# obc-v2_CM4-PinOut.net
KiCad netlist of a schematic drawn in Altium Designer
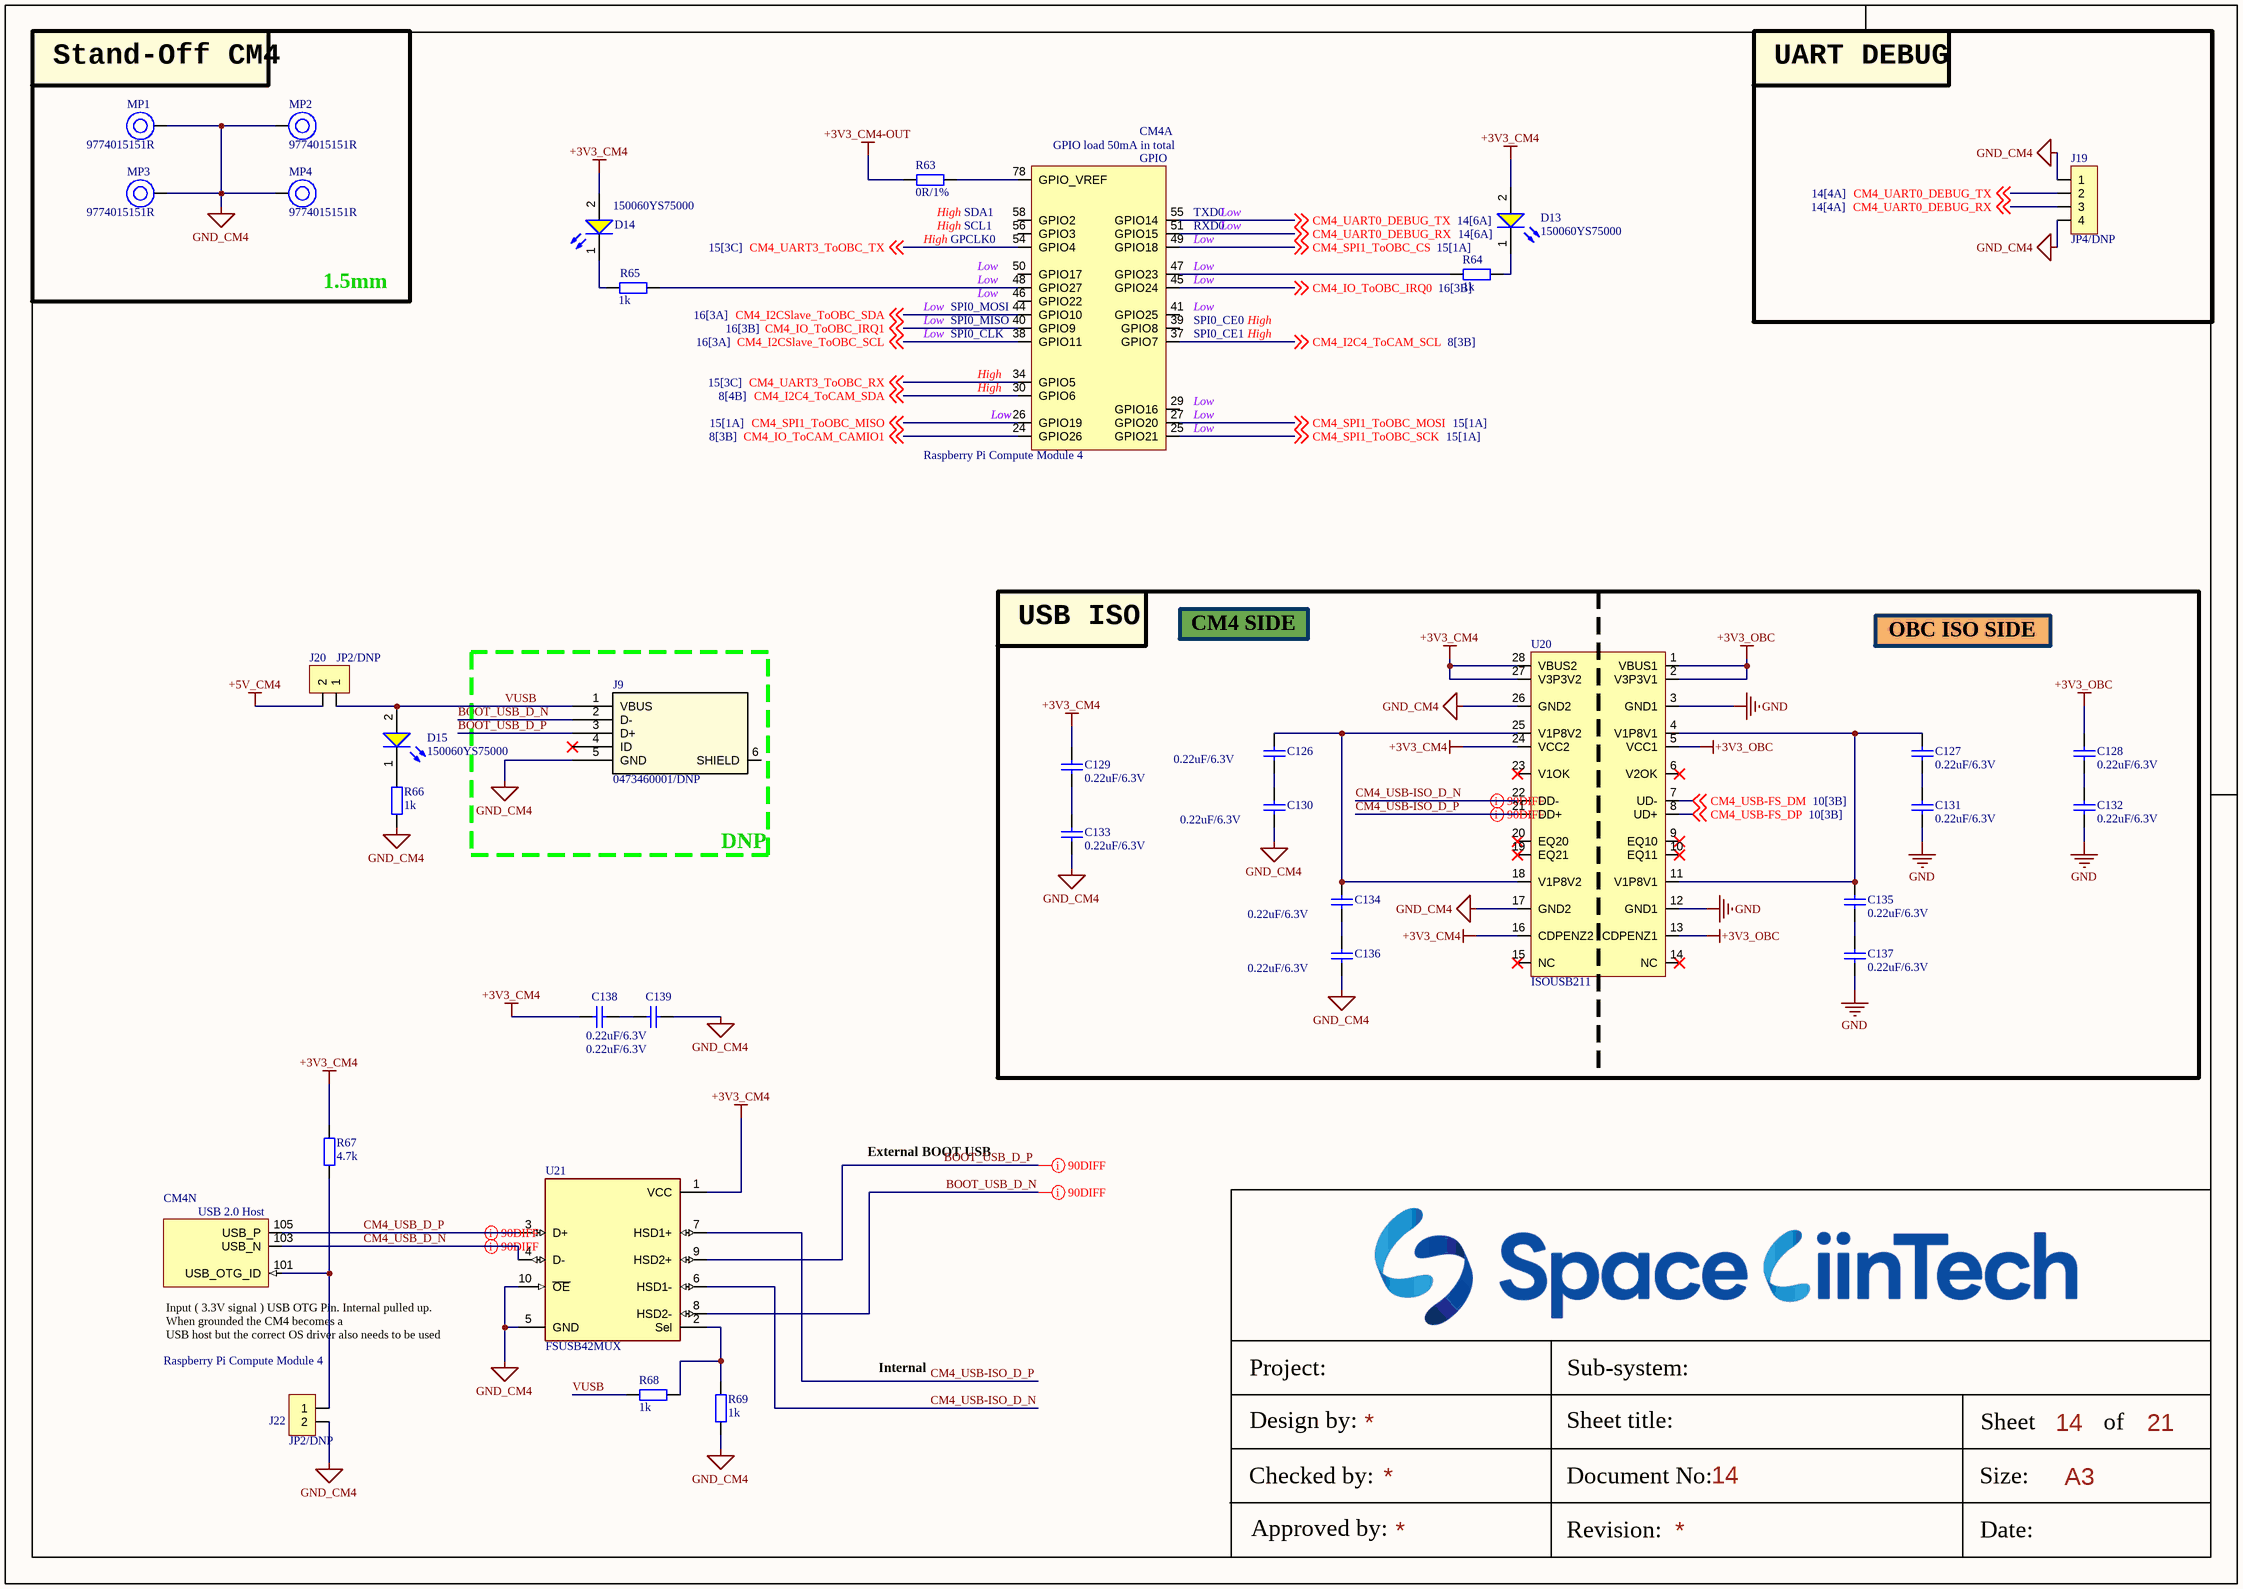
[diagram p0: obc-v2_CM4-PinOut.SchDoc]

(export (version "E")
  (design (tool "Eeschema 10.0.6"))
  (components
    (comp (ref "C126")
      (value "0.22uF/6.3V")
      (footprint "CAP_C_1005X60")
      (description "CAPC")
      (libsource (lib "Altium_Lib_by_KhueNguyenCreator") (part "Tu 0402 33nF 10V"))
    )
    (comp (ref "C127")
      (value "0.22uF/6.3V")
      (footprint "CAP_C_1005X60")
      (description "CAPC")
      (libsource (lib "Altium_Lib_by_KhueNguyenCreator") (part "Tu 0402 33nF 10V"))
    )
    (comp (ref "C128")
      (value "0.22uF/6.3V")
      (footprint "CAP_C_1005X60")
      (description "CAPC")
      (libsource (lib "Altium_Lib_by_KhueNguyenCreator") (part "Tu 0402 33nF 10V"))
    )
    (comp (ref "C129")
      (value "0.22uF/6.3V")
      (footprint "CAP_C_1005X60")
      (description "CAPC")
      (libsource (lib "Altium_Lib_by_KhueNguyenCreator") (part "Tu 0402 33nF 10V"))
    )
    (comp (ref "C130")
      (value "0.22uF/6.3V")
      (footprint "CAP_C_1005X60")
      (description "CAPC")
      (libsource (lib "Altium_Lib_by_KhueNguyenCreator") (part "Tu 0402 33nF 10V"))
    )
    (comp (ref "C131")
      (value "0.22uF/6.3V")
      (footprint "CAP_C_1005X60")
      (description "CAPC")
      (libsource (lib "Altium_Lib_by_KhueNguyenCreator") (part "Tu 0402 33nF 10V"))
    )
    (comp (ref "C132")
      (value "0.22uF/6.3V")
      (footprint "CAP_C_1005X60")
      (description "CAPC")
      (libsource (lib "Altium_Lib_by_KhueNguyenCreator") (part "Tu 0402 33nF 10V"))
    )
    (comp (ref "C133")
      (value "0.22uF/6.3V")
      (footprint "CAP_C_1005X60")
      (description "CAPC")
      (libsource (lib "Altium_Lib_by_KhueNguyenCreator") (part "Tu 0402 33nF 10V"))
    )
    (comp (ref "C134")
      (value "0.22uF/6.3V")
      (footprint "CAP_C_1005X60")
      (description "CAPC")
      (libsource (lib "Altium_Lib_by_KhueNguyenCreator") (part "Tu 0402 33nF 10V"))
    )
    (comp (ref "C135")
      (value "0.22uF/6.3V")
      (footprint "CAP_C_1005X60")
      (description "CAPC")
      (libsource (lib "Altium_Lib_by_KhueNguyenCreator") (part "Tu 0402 33nF 10V"))
    )
    (comp (ref "C136")
      (value "0.22uF/6.3V")
      (footprint "CAP_C_1005X60")
      (description "CAPC")
      (libsource (lib "Altium_Lib_by_KhueNguyenCreator") (part "Tu 0402 33nF 10V"))
    )
    (comp (ref "C137")
      (value "0.22uF/6.3V")
      (footprint "CAP_C_1005X60")
      (description "CAPC")
      (libsource (lib "Altium_Lib_by_KhueNguyenCreator") (part "Tu 0402 33nF 10V"))
    )
    (comp (ref "C138")
      (value "0.22uF/6.3V")
      (footprint "CAP_C_1005X60")
      (description "CAPC")
      (libsource (lib "Altium_Lib_by_KhueNguyenCreator") (part "Tu 0402 33nF 10V"))
    )
    (comp (ref "C139")
      (value "0.22uF/6.3V")
      (footprint "CAP_C_1005X60")
      (description "CAPC")
      (libsource (lib "Altium_Lib_by_KhueNguyenCreator") (part "Tu 0402 33nF 10V"))
    )
    (comp (ref "CM4")
      (value "Raspberry Pi Compute Module 4")
      (footprint "CM4-DF40HC(3.0)-100DS-0.4v_3mm_1.5mm")
      (description "Raspberry Pi Compute Module 4 by Amornthep Phunsin")
      (libsource (lib "CM4") (part "CM4"))
    )
    (comp (ref "D13")
      (value "150060YS75000")
      (footprint "WL-SMCW_0603_150060xx75000")
      (description "LED YELLOW CLEAR 0603 SMD")
      (libsource (lib "Altium Content Vault") (part "LED_Yellow_2A-1K"))
    )
    (comp (ref "D14")
      (value "150060YS75000")
      (footprint "WL-SMCW_0603_150060xx75000")
      (description "LED YELLOW CLEAR 0603 SMD")
      (libsource (lib "Altium Content Vault") (part "LED_Yellow_2A-1K"))
    )
    (comp (ref "D15")
      (value "150060YS75000")
      (footprint "WL-SMCW_0603_150060xx75000")
      (description "LED YELLOW CLEAR 0603 SMD")
      (libsource (lib "Altium Content Vault") (part "LED_Yellow_2A-1K"))
    )
    (comp (ref "J9")
      (value "0473460001/DNP")
      (footprint "47346-0001_MOL")
      (description "No Description Available")
      (libsource (lib "obc_ver2") (part "USB_micro"))
    )
    (comp (ref "J19")
      (value "JP4/DNP")
      (footprint "JP4-C1T")
      (description "WR-PHD 2.54 mm Angled Socket Header")
      (fields
        (field (name "MANUFACTURER") "Würth Elektronik eiSos GmbH")
        (field (name "PARTNO") "613004143121")
        (field (name "CREATED BY") "Karrer Zheng")
      )
      (libsource (lib "TechMT.VN_Lib_Project v2") (part "JP4"))
    )
    (comp (ref "J20")
      (value "JP2/DNP")
      (footprint "JP2-D1T")
      (description "WR-PHD 2.54 mm Angled Socket Header")
      (fields
        (field (name "MANUFACTURER") "Würth Elektronik eiSos GmbH")
        (field (name "PARTNO") "613002143121")
        (field (name "CREATED BY") "Karrer Zheng")
      )
      (libsource (lib "") (part "JP2_1"))
    )
    (comp (ref "J22")
      (value "JP2/DNP")
      (footprint "JP2-D1T")
      (description "WR-PHD 2.54 mm Angled Socket Header")
      (fields
        (field (name "MANUFACTURER") "Würth Elektronik eiSos GmbH")
        (field (name "PARTNO") "613002143121")
        (field (name "CREATED BY") "Karrer Zheng")
      )
      (libsource (lib "TechMT.VN_Lib") (part "JP2"))
    )
    (comp (ref "MP1")
      (value "9774015151R")
      (footprint "9774015151")
      (description "9774015151R WA-SMSI SMT Steel Spacer, M2.5 Internal non Stop")
      (libsource (lib "Altium Content Vault") (part "Spacer"))
    )
    (comp (ref "MP2")
      (value "9774015151R")
      (footprint "9774015151")
      (description "9774015151R WA-SMSI SMT Steel Spacer, M2.5 Internal non Stop")
      (libsource (lib "Altium Content Vault") (part "Spacer"))
    )
    (comp (ref "MP3")
      (value "9774015151R")
      (footprint "9774015151")
      (description "9774015151R WA-SMSI SMT Steel Spacer, M2.5 Internal non Stop")
      (libsource (lib "Altium Content Vault") (part "Spacer"))
    )
    (comp (ref "MP4")
      (value "9774015151R")
      (footprint "9774015151")
      (description "9774015151R WA-SMSI SMT Steel Spacer, M2.5 Internal non Stop")
      (libsource (lib "Altium Content Vault") (part "Spacer"))
    )
    (comp (ref "R63")
      (value "0R/1%")
      (footprint "RES_C_1608X60")
      (description "RES")
      (libsource (lib "Altium_Lib_by_KhueNguyenCreator") (part "Tro 0603 1% 10k"))
    )
    (comp (ref "R64")
      (value "1k")
      (footprint "RES_C_1608X60")
      (description "RES")
      (libsource (lib "Altium_Lib_by_KhueNguyenCreator") (part "Tro 0603 1% 10k"))
    )
    (comp (ref "R65")
      (value "1k")
      (footprint "RES_C_1608X60")
      (description "RES")
      (libsource (lib "Altium_Lib_by_KhueNguyenCreator") (part "Tro 0603 1% 10k"))
    )
    (comp (ref "R66")
      (value "1k")
      (footprint "RES_C_1608X60")
      (description "RES")
      (libsource (lib "Altium_Lib_by_KhueNguyenCreator") (part "Tro 0603 1% 10k"))
    )
    (comp (ref "R67")
      (value "4.7k")
      (footprint "RES_C_1608X60")
      (description "RES")
      (libsource (lib "Altium_Lib_by_KhueNguyenCreator") (part "Tro 0603 1% 10k"))
    )
    (comp (ref "R68")
      (value "1k")
      (footprint "RES_C_1608X60")
      (description "RES")
      (libsource (lib "Altium_Lib_by_KhueNguyenCreator") (part "Tro 0603 1% 10k"))
    )
    (comp (ref "R69")
      (value "1k")
      (footprint "RES_C_1608X60")
      (description "RES")
      (libsource (lib "Altium_Lib_by_KhueNguyenCreator") (part "Tro 0603 1% 10k"))
    )
    (comp (ref "U20")
      (value "ISOUSB211")
      (footprint "BSSOP_65P_750W_28")
      (libsource (lib "emmc_nofootprint") (part "ISOUSB211"))
    )
    (comp (ref "U21")
      (value "FSUSB42MUX")
      (footprint "FP-846AP-MFG")
      (description "IC USB SWITCH DPDT 10MSOP")
      (fields (field (name "VOLTAGE") "4.3V"))
      (libsource (lib "Altium Content Vault") (part "e0bd5e1b4e0e4edc77f3356c64bf8f9"))
    )
  )
  (nets
    (net (code "1") (name "+3V3_CM4") (class "Default")
      (node (ref "C129") (pin "1") (pinfunction "1_1") (pintype "passive"))
      (node (ref "C138") (pin "1") (pinfunction "1_1") (pintype "passive"))
      (node (ref "D13") (pin "2") (pinfunction "A_2") (pintype "passive"))
      (node (ref "D14") (pin "2") (pinfunction "A_2") (pintype "passive"))
      (node (ref "R67") (pin "1") (pinfunction "1_1") (pintype "passive"))
      (node (ref "U20") (pin "16") (pinfunction "CDPENZ2_16") (pintype "passive"))
      (node (ref "U20") (pin "24") (pinfunction "VCC2_24") (pintype "passive"))
      (node (ref "U20") (pin "27") (pinfunction "V3P3V2_27") (pintype "passive"))
      (node (ref "U20") (pin "28") (pinfunction "VBUS2_28") (pintype "passive"))
      (node (ref "U21") (pin "1") (pinfunction "VCC_1") (pintype "power_in"))
    )
    (net (code "2") (name "+3V3_CM4-OUT") (class "Default")
      (node (ref "R63") (pin "1") (pinfunction "1_1") (pintype "passive"))
    )
    (net (code "3") (name "+3V3_OBC") (class "Default")
      (node (ref "C128") (pin "1") (pinfunction "1_1") (pintype "passive"))
      (node (ref "U20") (pin "1") (pinfunction "VBUS1_1") (pintype "passive"))
      (node (ref "U20") (pin "13") (pinfunction "CDPENZ1_13") (pintype "passive"))
      (node (ref "U20") (pin "2") (pinfunction "V3P3V1_2") (pintype "passive"))
      (node (ref "U20") (pin "5") (pinfunction "VCC1_5") (pintype "passive"))
    )
    (net (code "4") (name "+5V_CM4") (class "Default")
      (node (ref "J20") (pin "2") (pinfunction "2_2") (pintype "passive"))
    )
    (net (code "5") (name "/BOOT_USB_D_N") (class "Default")
      (node (ref "J9") (pin "2") (pinfunction "D-_2") (pintype "passive"))
      (node (ref "U21") (pin "8") (pinfunction "HSD2-_8") (pintype "bidirectional"))
    )
    (net (code "6") (name "/BOOT_USB_D_P") (class "Default")
      (node (ref "J9") (pin "3") (pinfunction "D+_3") (pintype "passive"))
      (node (ref "U21") (pin "9") (pinfunction "HSD2+_9") (pintype "bidirectional"))
    )
    (net (code "7") (name "/CM4_USB-ISO_D_N") (class "Default")
      (node (ref "U20") (pin "22") (pinfunction "DD-_22") (pintype "passive"))
      (node (ref "U21") (pin "6") (pinfunction "HSD1-_6") (pintype "bidirectional"))
    )
    (net (code "8") (name "/CM4_USB-ISO_D_P") (class "Default")
      (node (ref "U20") (pin "21") (pinfunction "DD+_21") (pintype "passive"))
      (node (ref "U21") (pin "7") (pinfunction "HSD1+_7") (pintype "bidirectional"))
    )
    (net (code "9") (name "/CM4_USB_D_N") (class "Default")
      (node (ref "CM4") (pin "103") (pinfunction "USB_N_103") (pintype "passive"))
      (node (ref "U21") (pin "4") (pinfunction "D-_4") (pintype "bidirectional"))
    )
    (net (code "10") (name "/CM4_USB_D_P") (class "Default")
      (node (ref "CM4") (pin "105") (pinfunction "USB_P_105") (pintype "passive"))
      (node (ref "U21") (pin "3") (pinfunction "D+_3") (pintype "bidirectional"))
    )
    (net (code "11") (name "/VUSB") (class "Default")
      (node (ref "D15") (pin "2") (pinfunction "A_2") (pintype "passive"))
      (node (ref "J20") (pin "1") (pinfunction "1_1") (pintype "passive"))
      (node (ref "J9") (pin "1") (pinfunction "VBUS_1") (pintype "passive"))
      (node (ref "R68") (pin "1") (pinfunction "1_1") (pintype "passive"))
    )
    (net (code "12") (name "CM4_I2C4_ToCAM_SCL") (class "Default")
      (node (ref "CM4") (pin "37") (pinfunction "GPIO7_37") (pintype "passive"))
    )
    (net (code "13") (name "CM4_I2C4_ToCAM_SDA") (class "Default")
      (node (ref "CM4") (pin "30") (pinfunction "GPIO6_30") (pintype "passive"))
    )
    (net (code "14") (name "CM4_I2CSlave_ToOBC_SCL") (class "Default")
      (node (ref "CM4") (pin "38") (pinfunction "GPIO11_38") (pintype "passive"))
    )
    (net (code "15") (name "CM4_I2CSlave_ToOBC_SDA") (class "Default")
      (node (ref "CM4") (pin "44") (pinfunction "GPIO10_44") (pintype "passive"))
    )
    (net (code "16") (name "CM4_IO_ToCAM_CAMIO1") (class "Default")
      (node (ref "CM4") (pin "24") (pinfunction "GPIO26_24") (pintype "passive"))
    )
    (net (code "17") (name "CM4_IO_ToOBC_IRQ0") (class "Default")
      (node (ref "CM4") (pin "45") (pinfunction "GPIO24_45") (pintype "passive"))
    )
    (net (code "18") (name "CM4_IO_ToOBC_IRQ1") (class "Default")
      (node (ref "CM4") (pin "40") (pinfunction "GPIO9_40") (pintype "passive"))
    )
    (net (code "19") (name "CM4_SPI1_ToOBC_CS") (class "Default")
      (node (ref "CM4") (pin "49") (pinfunction "GPIO18_49") (pintype "passive"))
    )
    (net (code "20") (name "CM4_SPI1_ToOBC_MISO") (class "Default")
      (node (ref "CM4") (pin "26") (pinfunction "GPIO19_26") (pintype "passive"))
    )
    (net (code "21") (name "CM4_SPI1_ToOBC_MOSI") (class "Default")
      (node (ref "CM4") (pin "27") (pinfunction "GPIO20_27") (pintype "passive"))
    )
    (net (code "22") (name "CM4_SPI1_ToOBC_SCK") (class "Default")
      (node (ref "CM4") (pin "25") (pinfunction "GPIO21_25") (pintype "passive"))
    )
    (net (code "23") (name "CM4_UART0_DEBUG_RX") (class "Default")
      (node (ref "CM4") (pin "51") (pinfunction "GPIO15_51") (pintype "passive"))
      (node (ref "J19") (pin "3") (pinfunction "3_3") (pintype "passive"))
    )
    (net (code "24") (name "CM4_UART0_DEBUG_TX") (class "Default")
      (node (ref "CM4") (pin "55") (pinfunction "GPIO14_55") (pintype "passive"))
      (node (ref "J19") (pin "2") (pinfunction "2_2") (pintype "passive"))
    )
    (net (code "25") (name "CM4_UART3_ToOBC_RX") (class "Default")
      (node (ref "CM4") (pin "34") (pinfunction "GPIO5_34") (pintype "passive"))
    )
    (net (code "26") (name "CM4_UART3_ToOBC_TX") (class "Default")
      (node (ref "CM4") (pin "54") (pinfunction "GPIO4_54") (pintype "passive"))
    )
    (net (code "27") (name "CM4_USB-FS_DM") (class "Default")
      (node (ref "U20") (pin "7") (pinfunction "UD-_7") (pintype "passive"))
    )
    (net (code "28") (name "CM4_USB-FS_DP") (class "Default")
      (node (ref "U20") (pin "8") (pinfunction "UD+_8") (pintype "passive"))
    )
    (net (code "29") (name "GND") (class "Default")
      (node (ref "C131") (pin "2") (pinfunction "2_2") (pintype "passive"))
      (node (ref "C132") (pin "2") (pinfunction "2_2") (pintype "passive"))
      (node (ref "C137") (pin "2") (pinfunction "2_2") (pintype "passive"))
      (node (ref "U20") (pin "12") (pinfunction "GND1_12") (pintype "passive"))
      (node (ref "U20") (pin "3") (pinfunction "GND1_3") (pintype "passive"))
    )
    (net (code "30") (name "GND_CM4") (class "Default")
      (node (ref "C130") (pin "2") (pinfunction "2_2") (pintype "passive"))
      (node (ref "C133") (pin "2") (pinfunction "2_2") (pintype "passive"))
      (node (ref "C136") (pin "2") (pinfunction "2_2") (pintype "passive"))
      (node (ref "C139") (pin "2") (pinfunction "2_2") (pintype "passive"))
      (node (ref "J19") (pin "1") (pinfunction "1_1") (pintype "passive"))
      (node (ref "J19") (pin "4") (pinfunction "4_4") (pintype "passive"))
      (node (ref "J22") (pin "2") (pinfunction "2_2") (pintype "passive"))
      (node (ref "J9") (pin "5") (pinfunction "GND_5") (pintype "power_in"))
      (node (ref "MP1") (pin "1") (pinfunction "1_1") (pintype "passive"))
      (node (ref "MP2") (pin "1") (pinfunction "1_1") (pintype "passive"))
      (node (ref "MP3") (pin "1") (pinfunction "1_1") (pintype "passive"))
      (node (ref "MP4") (pin "1") (pinfunction "1_1") (pintype "passive"))
      (node (ref "R66") (pin "2") (pinfunction "2_2") (pintype "passive"))
      (node (ref "R69") (pin "2") (pinfunction "2_2") (pintype "passive"))
      (node (ref "U20") (pin "17") (pinfunction "GND2_17") (pintype "passive"))
      (node (ref "U20") (pin "26") (pinfunction "GND2_26") (pintype "passive"))
      (node (ref "U21") (pin "10") (pinfunction "~{OE}_10") (pintype "input"))
      (node (ref "U21") (pin "5") (pinfunction "GND_5") (pintype "power_in"))
    )
    (net (code "31") (name "Net-(C126-Pad1)") (class "Default")
      (node (ref "C126") (pin "1") (pinfunction "1_1") (pintype "passive"))
      (node (ref "C134") (pin "1") (pinfunction "1_1") (pintype "passive"))
      (node (ref "U20") (pin "18") (pinfunction "V1P8V2_18") (pintype "passive"))
      (node (ref "U20") (pin "25") (pinfunction "V1P8V2_25") (pintype "passive"))
    )
    (net (code "32") (name "Net-(C126-Pad2)") (class "Default")
      (node (ref "C126") (pin "2") (pinfunction "2_2") (pintype "passive"))
      (node (ref "C130") (pin "1") (pinfunction "1_1") (pintype "passive"))
    )
    (net (code "33") (name "Net-(C127-Pad1)") (class "Default")
      (node (ref "C127") (pin "1") (pinfunction "1_1") (pintype "passive"))
      (node (ref "C135") (pin "1") (pinfunction "1_1") (pintype "passive"))
      (node (ref "U20") (pin "11") (pinfunction "V1P8V1_11") (pintype "passive"))
      (node (ref "U20") (pin "4") (pinfunction "V1P8V1_4") (pintype "passive"))
    )
    (net (code "34") (name "Net-(C127-Pad2)") (class "Default")
      (node (ref "C127") (pin "2") (pinfunction "2_2") (pintype "passive"))
      (node (ref "C131") (pin "1") (pinfunction "1_1") (pintype "passive"))
    )
    (net (code "35") (name "Net-(C128-Pad2)") (class "Default")
      (node (ref "C128") (pin "2") (pinfunction "2_2") (pintype "passive"))
      (node (ref "C132") (pin "1") (pinfunction "1_1") (pintype "passive"))
    )
    (net (code "36") (name "Net-(C129-Pad2)") (class "Default")
      (node (ref "C129") (pin "2") (pinfunction "2_2") (pintype "passive"))
      (node (ref "C133") (pin "1") (pinfunction "1_1") (pintype "passive"))
    )
    (net (code "37") (name "Net-(C134-Pad2)") (class "Default")
      (node (ref "C134") (pin "2") (pinfunction "2_2") (pintype "passive"))
      (node (ref "C136") (pin "1") (pinfunction "1_1") (pintype "passive"))
    )
    (net (code "38") (name "Net-(C135-Pad2)") (class "Default")
      (node (ref "C135") (pin "2") (pinfunction "2_2") (pintype "passive"))
      (node (ref "C137") (pin "1") (pinfunction "1_1") (pintype "passive"))
    )
    (net (code "39") (name "Net-(C138-Pad2)") (class "Default")
      (node (ref "C138") (pin "2") (pinfunction "2_2") (pintype "passive"))
      (node (ref "C139") (pin "1") (pinfunction "1_1") (pintype "passive"))
    )
    (net (code "40") (name "Net-(CM4A-GPIO23)") (class "Default")
      (node (ref "CM4") (pin "47") (pinfunction "GPIO23_47") (pintype "passive"))
      (node (ref "R64") (pin "2") (pinfunction "2_2") (pintype "passive"))
    )
    (net (code "41") (name "Net-(CM4A-GPIO27)") (class "Default")
      (node (ref "CM4") (pin "48") (pinfunction "GPIO27_48") (pintype "passive"))
      (node (ref "R65") (pin "2") (pinfunction "2_2") (pintype "passive"))
    )
    (net (code "42") (name "Net-(CM4A-GPIO_VREF)") (class "Default")
      (node (ref "CM4") (pin "78") (pinfunction "GPIO_VREF_78") (pintype "power_in"))
      (node (ref "R63") (pin "2") (pinfunction "2_2") (pintype "passive"))
    )
    (net (code "43") (name "Net-(CM4N-USB_OTG_ID)") (class "Default")
      (node (ref "CM4") (pin "101") (pinfunction "USB_OTG_ID_101") (pintype "input"))
      (node (ref "J22") (pin "1") (pinfunction "1_1") (pintype "passive"))
      (node (ref "R67") (pin "2") (pinfunction "2_2") (pintype "passive"))
    )
    (net (code "44") (name "Net-(D13-K)") (class "Default")
      (node (ref "D13") (pin "1") (pinfunction "K_1") (pintype "passive"))
      (node (ref "R64") (pin "1") (pinfunction "1_1") (pintype "passive"))
    )
    (net (code "45") (name "Net-(D14-K)") (class "Default")
      (node (ref "D14") (pin "1") (pinfunction "K_1") (pintype "passive"))
      (node (ref "R65") (pin "1") (pinfunction "1_1") (pintype "passive"))
    )
    (net (code "46") (name "Net-(D15-K)") (class "Default")
      (node (ref "D15") (pin "1") (pinfunction "K_1") (pintype "passive"))
      (node (ref "R66") (pin "1") (pinfunction "1_1") (pintype "passive"))
    )
    (net (code "47") (name "Net-(U21-Sel)") (class "Default")
      (node (ref "R68") (pin "2") (pinfunction "2_2") (pintype "passive"))
      (node (ref "R69") (pin "1") (pinfunction "1_1") (pintype "passive"))
      (node (ref "U21") (pin "2") (pinfunction "Sel_2") (pintype "passive"))
    )
    (net (code "48") (name "unconnected-(CM4A-GPIO2-Pad58)") (class "Default")
      (node (ref "CM4") (pin "58") (pinfunction "GPIO2_58") (pintype "passive"))
    )
    (net (code "49") (name "unconnected-(CM4A-GPIO3-Pad56)") (class "Default")
      (node (ref "CM4") (pin "56") (pinfunction "GPIO3_56") (pintype "passive"))
    )
    (net (code "50") (name "unconnected-(CM4A-GPIO8-Pad39)") (class "Default")
      (node (ref "CM4") (pin "39") (pinfunction "GPIO8_39") (pintype "passive"))
    )
    (net (code "51") (name "unconnected-(CM4A-GPIO16-Pad29)") (class "Default")
      (node (ref "CM4") (pin "29") (pinfunction "GPIO16_29") (pintype "passive"))
    )
    (net (code "52") (name "unconnected-(CM4A-GPIO17-Pad50)") (class "Default")
      (node (ref "CM4") (pin "50") (pinfunction "GPIO17_50") (pintype "passive"))
    )
    (net (code "53") (name "unconnected-(CM4A-GPIO22-Pad46)") (class "Default")
      (node (ref "CM4") (pin "46") (pinfunction "GPIO22_46") (pintype "passive"))
    )
    (net (code "54") (name "unconnected-(CM4A-GPIO25-Pad41)") (class "Default")
      (node (ref "CM4") (pin "41") (pinfunction "GPIO25_41") (pintype "passive"))
    )
    (net (code "55") (name "unconnected-(J9-ID-Pad4)") (class "Default")
      (node (ref "J9") (pin "4") (pinfunction "ID_4") (pintype "passive+no_connect"))
    )
    (net (code "56") (name "unconnected-(J9-SHIELD-Pad6)") (class "Default")
      (node (ref "J9") (pin "6") (pinfunction "SHIELD_6") (pintype "passive"))
    )
    (net (code "57") (name "unconnected-(U20-EQ10-Pad9)") (class "Default")
      (node (ref "U20") (pin "9") (pinfunction "EQ10_9") (pintype "passive+no_connect"))
    )
    (net (code "58") (name "unconnected-(U20-EQ11-Pad10)") (class "Default")
      (node (ref "U20") (pin "10") (pinfunction "EQ11_10") (pintype "passive+no_connect"))
    )
    (net (code "59") (name "unconnected-(U20-EQ20-Pad20)") (class "Default")
      (node (ref "U20") (pin "20") (pinfunction "EQ20_20") (pintype "passive+no_connect"))
    )
    (net (code "60") (name "unconnected-(U20-EQ21-Pad19)") (class "Default")
      (node (ref "U20") (pin "19") (pinfunction "EQ21_19") (pintype "passive+no_connect"))
    )
    (net (code "61") (name "unconnected-(U20-NC-Pad14)") (class "Default")
      (node (ref "U20") (pin "14") (pinfunction "NC_14") (pintype "passive+no_connect"))
    )
    (net (code "62") (name "unconnected-(U20-NC-Pad15)") (class "Default")
      (node (ref "U20") (pin "15") (pinfunction "NC_15") (pintype "passive+no_connect"))
    )
    (net (code "63") (name "unconnected-(U20-V1OK-Pad23)") (class "Default")
      (node (ref "U20") (pin "23") (pinfunction "V1OK_23") (pintype "passive+no_connect"))
    )
    (net (code "64") (name "unconnected-(U20-V2OK-Pad6)") (class "Default")
      (node (ref "U20") (pin "6") (pinfunction "V2OK_6") (pintype "passive+no_connect"))
    )
  )
)
